# host_board.net
KiCad netlist of a schematic drawn in Altium Designer
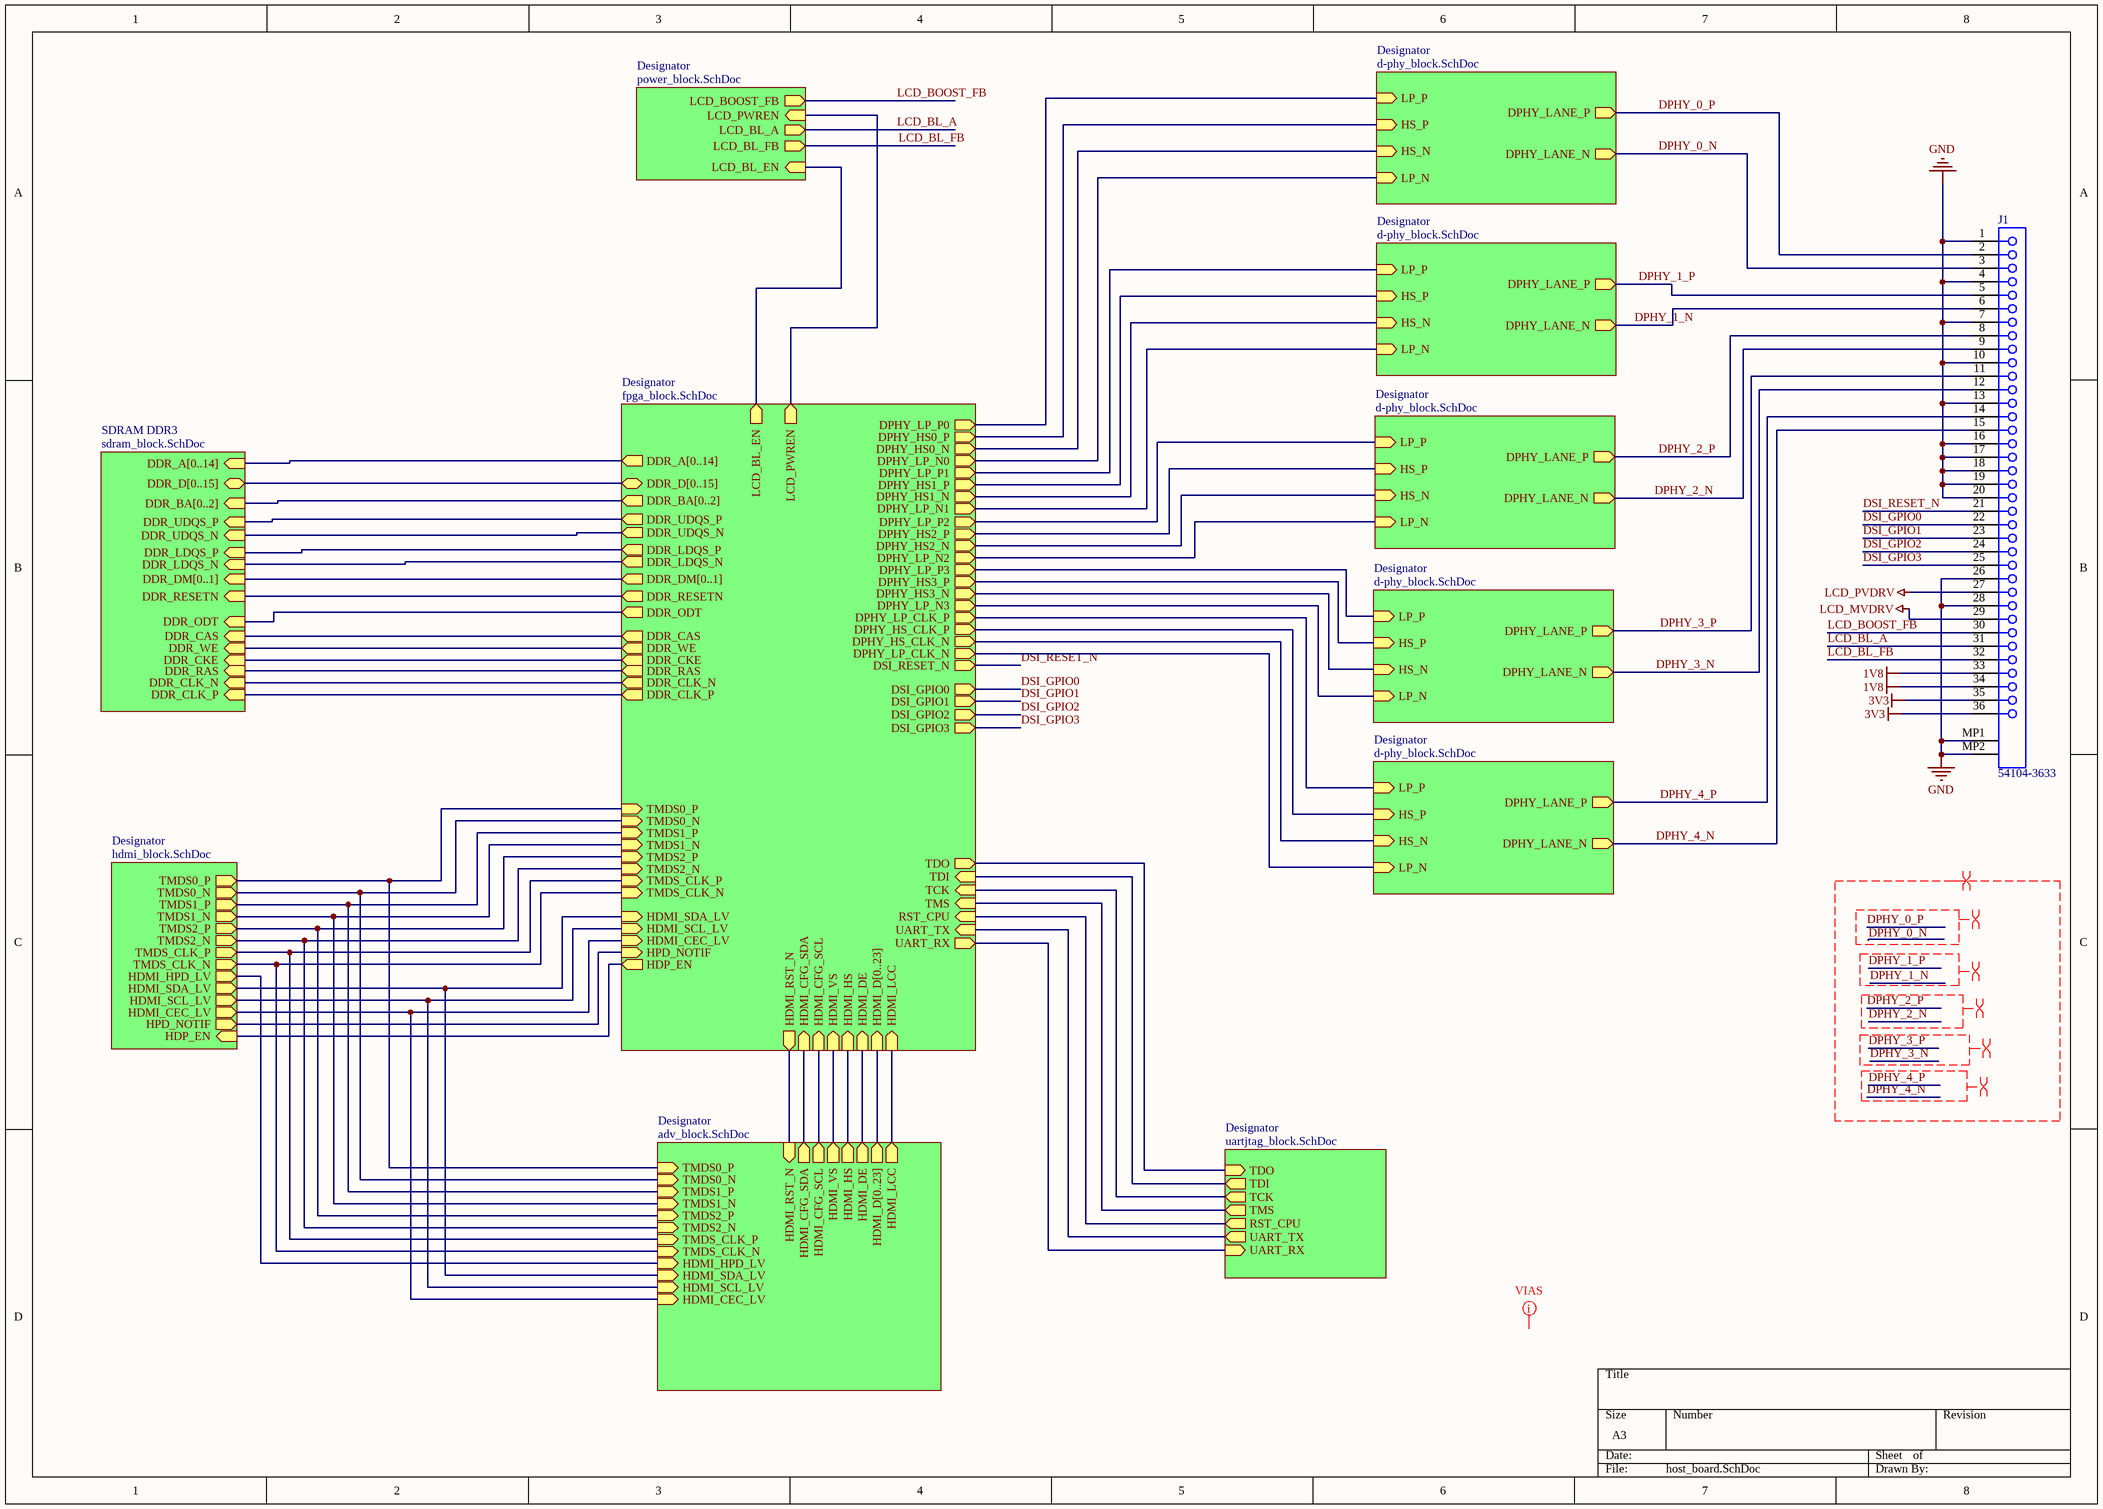
[diagram p0: host_board.SchDoc]

(export (version "E")
  (design (tool "Eeschema 10.0.6"))
  (components
    (comp (ref "J1")
      (value "54104-3633")
      (footprint "MOLX-54104-3633")
      (fields (field (name "MANUFACTURER") "Molex"))
      (libsource (lib "Molex FFC - FPC Connectors (SMT)") (part "54104-3633"))
    )
  )
  (nets
    (net (code "17") (name "/DPHY_0_N") (class "Default")
      (node (ref "J1") (pin "3") (pinfunction "3_3") (pintype "passive"))
    )
    (net (code "18") (name "/DPHY_0_P") (class "Default")
      (node (ref "J1") (pin "2") (pinfunction "2_2") (pintype "passive"))
    )
    (net (code "19") (name "/DPHY_1_N") (class "Default")
      (node (ref "J1") (pin "6") (pinfunction "6_6") (pintype "passive"))
    )
    (net (code "20") (name "/DPHY_1_P") (class "Default")
      (node (ref "J1") (pin "5") (pinfunction "5_5") (pintype "passive"))
    )
    (net (code "21") (name "/DPHY_2_N") (class "Default")
      (node (ref "J1") (pin "9") (pinfunction "9_9") (pintype "passive"))
    )
    (net (code "22") (name "/DPHY_2_P") (class "Default")
      (node (ref "J1") (pin "8") (pinfunction "8_8") (pintype "passive"))
    )
    (net (code "23") (name "/DPHY_3_N") (class "Default")
      (node (ref "J1") (pin "12") (pinfunction "12_12") (pintype "passive"))
    )
    (net (code "24") (name "/DPHY_3_P") (class "Default")
      (node (ref "J1") (pin "11") (pinfunction "11_11") (pintype "passive"))
    )
    (net (code "25") (name "/DPHY_4_N") (class "Default")
      (node (ref "J1") (pin "15") (pinfunction "15_15") (pintype "passive"))
    )
    (net (code "26") (name "/DPHY_4_P") (class "Default")
      (node (ref "J1") (pin "14") (pinfunction "14_14") (pintype "passive"))
    )
    (net (code "53") (name "/DSI_GPIO0") (class "Default")
      (node (ref "J1") (pin "22") (pinfunction "22_22") (pintype "passive"))
    )
    (net (code "54") (name "/DSI_GPIO1") (class "Default")
      (node (ref "J1") (pin "23") (pinfunction "23_23") (pintype "passive"))
    )
    (net (code "55") (name "/DSI_GPIO2") (class "Default")
      (node (ref "J1") (pin "24") (pinfunction "24_24") (pintype "passive"))
    )
    (net (code "56") (name "/DSI_GPIO3") (class "Default")
      (node (ref "J1") (pin "25") (pinfunction "25_25") (pintype "passive"))
    )
    (net (code "57") (name "/DSI_RESET_N") (class "Default")
      (node (ref "J1") (pin "21") (pinfunction "21_21") (pintype "passive"))
    )
    (net (code "72") (name "/LCD_BL_A") (class "Default")
      (node (ref "J1") (pin "31") (pinfunction "31_31") (pintype "passive"))
    )
    (net (code "74") (name "/LCD_BL_FB") (class "Default")
      (node (ref "J1") (pin "32") (pinfunction "32_32") (pintype "passive"))
    )
    (net (code "75") (name "/LCD_BOOST_FB") (class "Default")
      (node (ref "J1") (pin "30") (pinfunction "30_30") (pintype "passive"))
    )
    (net (code "92") (name "1V8") (class "Default")
      (node (ref "J1") (pin "33") (pinfunction "33_33") (pintype "passive"))
      (node (ref "J1") (pin "34") (pinfunction "34_34") (pintype "passive"))
    )
    (net (code "93") (name "3V3") (class "Default")
      (node (ref "J1") (pin "35") (pinfunction "35_35") (pintype "passive"))
      (node (ref "J1") (pin "36") (pinfunction "36_36") (pintype "passive"))
    )
    (net (code "94") (name "GND") (class "Default")
      (node (ref "J1") (pin "1") (pinfunction "1_1") (pintype "passive"))
      (node (ref "J1") (pin "10") (pinfunction "10_10") (pintype "passive"))
      (node (ref "J1") (pin "13") (pinfunction "13_13") (pintype "passive"))
      (node (ref "J1") (pin "16") (pinfunction "16_16") (pintype "passive"))
      (node (ref "J1") (pin "17") (pinfunction "17_17") (pintype "passive"))
      (node (ref "J1") (pin "18") (pinfunction "18_18") (pintype "passive"))
      (node (ref "J1") (pin "19") (pinfunction "19_19") (pintype "passive"))
      (node (ref "J1") (pin "20") (pinfunction "20_20") (pintype "passive"))
      (node (ref "J1") (pin "26") (pinfunction "26_26") (pintype "passive"))
      (node (ref "J1") (pin "28") (pinfunction "28_28") (pintype "passive"))
      (node (ref "J1") (pin "4") (pinfunction "4_4") (pintype "passive"))
      (node (ref "J1") (pin "7") (pinfunction "7_7") (pintype "passive"))
      (node (ref "J1") (pin "MP1") (pinfunction "MP1_MP1") (pintype "passive"))
      (node (ref "J1") (pin "MP2") (pinfunction "MP2_MP2") (pintype "passive"))
    )
    (net (code "95") (name "LCD_MVDRV") (class "Default")
      (node (ref "J1") (pin "29") (pinfunction "29_29") (pintype "passive"))
    )
    (net (code "96") (name "LCD_PVDRV") (class "Default")
      (node (ref "J1") (pin "27") (pinfunction "27_27") (pintype "passive"))
    )
  )
)
